# Inverter.net
KiCad netlist of a schematic drawn in Altium Designer
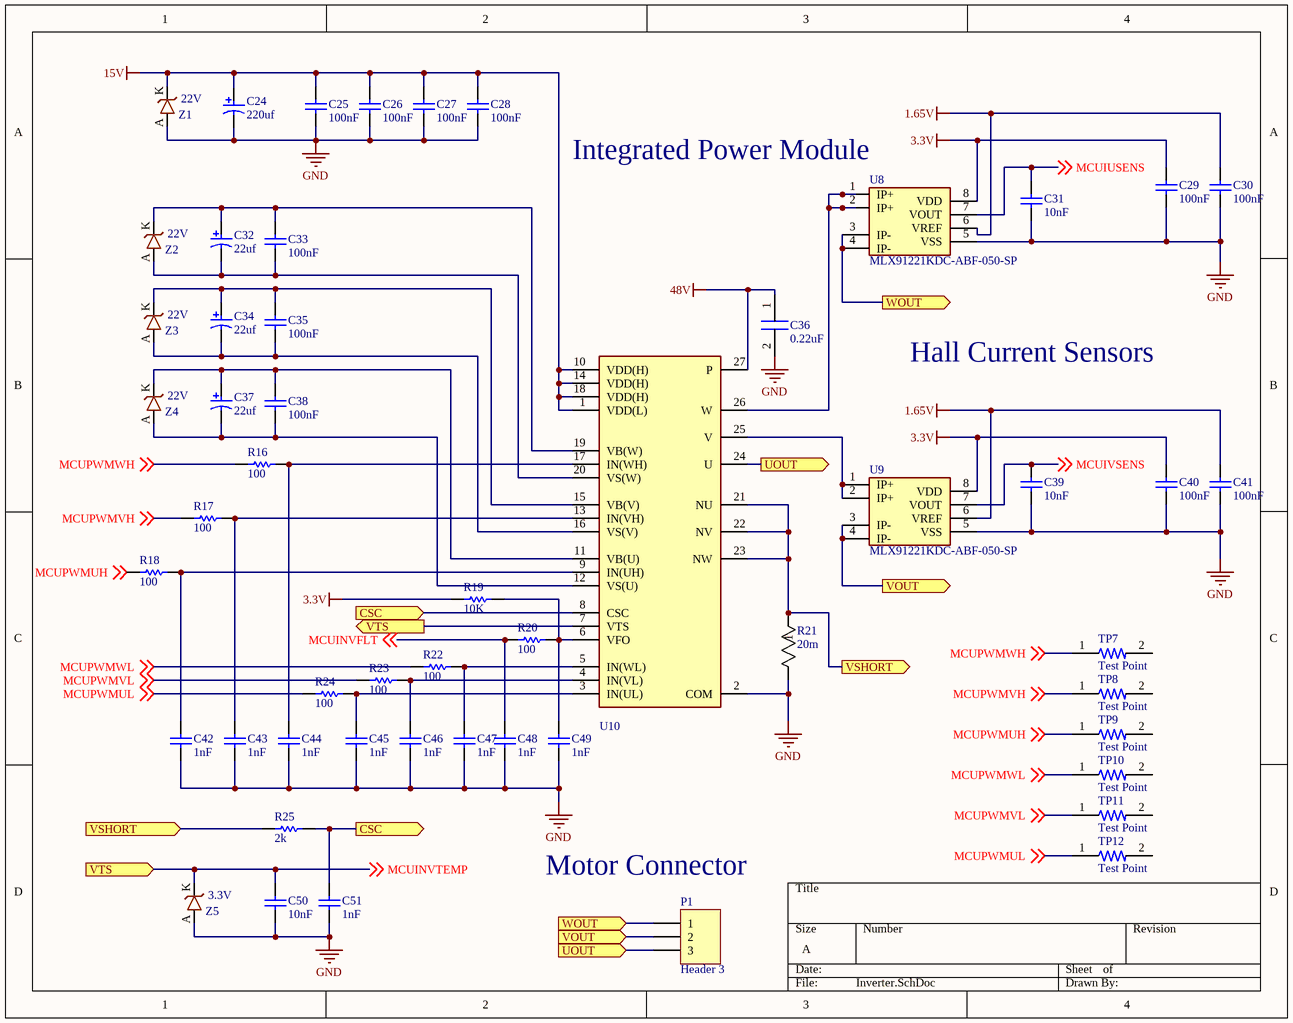
[diagram p0: Inverter.SchDoc]

(export (version "E")
  (design (tool "Eeschema 10.0.6"))
  (components
    (comp (ref "C24")
      (value "220uf")
      (footprint "PNSC-ECA-1VM221-2")
      (description "Aluminum Electrolytic Capacitor, 220 uF, +/- 20%, 35 V, -40 to 85 degC, 2-Pin THD, RoHS, Bulk")
      (fields (field (name "MANUFACTURER") "Panasonic"))
      (libsource (lib "Altium Content Vault") (part "CAP-P-2"))
    )
    (comp (ref "C25")
      (value "100nF")
      (footprint "CAPC1609X100X15LL20")
      (fields
        (field (name "MANUFACTURER") "AVX Interconnect / Elco")
        (field (name "PART NUMBER") "TACL105M006XTA")
      )
      (libsource (lib "Altium Content Vault") (part "CAP"))
    )
    (comp (ref "C26")
      (value "100nF")
      (footprint "CAPC1609X100X15LL20")
      (fields
        (field (name "MANUFACTURER") "AVX Interconnect / Elco")
        (field (name "PART NUMBER") "TACL105M006XTA")
      )
      (libsource (lib "Altium Content Vault") (part "CAP"))
    )
    (comp (ref "C27")
      (value "100nF")
      (footprint "CAPC1609X100X15LL20")
      (fields
        (field (name "MANUFACTURER") "AVX Interconnect / Elco")
        (field (name "PART NUMBER") "TACL105M006XTA")
      )
      (libsource (lib "Altium Content Vault") (part "CAP"))
    )
    (comp (ref "C28")
      (value "100nF")
      (footprint "CAPC1609X100X15LL20")
      (fields
        (field (name "MANUFACTURER") "AVX Interconnect / Elco")
        (field (name "PART NUMBER") "TACL105M006XTA")
      )
      (libsource (lib "Altium Content Vault") (part "CAP"))
    )
    (comp (ref "C29")
      (value "100nF")
      (footprint "CAPC1609X100X15LL20")
      (fields
        (field (name "MANUFACTURER") "AVX Interconnect / Elco")
        (field (name "PART NUMBER") "TACL105M006XTA")
      )
      (libsource (lib "Altium Content Vault") (part "CAP"))
    )
    (comp (ref "C30")
      (value "100nF")
      (footprint "CAPC1609X100X15LL20")
      (fields
        (field (name "MANUFACTURER") "AVX Interconnect / Elco")
        (field (name "PART NUMBER") "TACL105M006XTA")
      )
      (libsource (lib "Altium Content Vault") (part "CAP"))
    )
    (comp (ref "C31")
      (value "10nF")
      (footprint "CAPC1609X100X15LL20")
      (fields
        (field (name "MANUFACTURER") "AVX Interconnect / Elco")
        (field (name "PART NUMBER") "TACL105M006XTA")
      )
      (libsource (lib "Altium Content Vault") (part "CAP"))
    )
    (comp (ref "C32")
      (value "22uf")
      (footprint "CAPPR55-200-1100X500X1200")
      (description "Aluminum Electrolytic Capacitor, 22 uF, +/- 20%, 50 V, -40 to 85 degC, 2-Pin THD, RoHS, Bulk")
      (fields (field (name "VOLTAGE") "50V") (field (name "MANUFACTURER") "Panasonic"))
      (libsource (lib "Altium Content Vault") (part "CAP-P-2"))
    )
    (comp (ref "C33")
      (value "100nF")
      (footprint "CAPC1609X100X15LL20")
      (fields
        (field (name "MANUFACTURER") "AVX Interconnect / Elco")
        (field (name "PART NUMBER") "TACL105M006XTA")
      )
      (libsource (lib "Altium Content Vault") (part "CAP"))
    )
    (comp (ref "C34")
      (value "22uf")
      (footprint "CAPPR55-200-1100X500X1200")
      (description "Aluminum Electrolytic Capacitor, 22 uF, +/- 20%, 50 V, -40 to 85 degC, 2-Pin THD, RoHS, Bulk")
      (fields (field (name "VOLTAGE") "50V") (field (name "MANUFACTURER") "Panasonic"))
      (libsource (lib "Altium Content Vault") (part "CAP-P-2"))
    )
    (comp (ref "C35")
      (value "100nF")
      (footprint "CAPC1609X100X15LL20")
      (fields
        (field (name "MANUFACTURER") "AVX Interconnect / Elco")
        (field (name "PART NUMBER") "TACL105M006XTA")
      )
      (libsource (lib "Altium Content Vault") (part "CAP"))
    )
    (comp (ref "C36")
      (value "0.22uF")
      (footprint "B32652A3224K000")
      (description "Capacitor, Film, 15mm leads")
      (libsource (lib "ee_453_yourname") (part "B32652A3224K000"))
    )
    (comp (ref "C37")
      (value "22uf")
      (footprint "CAPPR55-200-1100X500X1200")
      (description "Aluminum Electrolytic Capacitor, 22 uF, +/- 20%, 50 V, -40 to 85 degC, 2-Pin THD, RoHS, Bulk")
      (fields (field (name "VOLTAGE") "50V") (field (name "MANUFACTURER") "Panasonic"))
      (libsource (lib "Altium Content Vault") (part "CAP-P-2"))
    )
    (comp (ref "C38")
      (value "100nF")
      (footprint "CAPC1609X100X15LL20")
      (fields
        (field (name "MANUFACTURER") "AVX Interconnect / Elco")
        (field (name "PART NUMBER") "TACL105M006XTA")
      )
      (libsource (lib "Altium Content Vault") (part "CAP"))
    )
    (comp (ref "C39")
      (value "10nF")
      (footprint "CAPC1609X100X15LL20")
      (fields
        (field (name "MANUFACTURER") "AVX Interconnect / Elco")
        (field (name "PART NUMBER") "TACL105M006XTA")
      )
      (libsource (lib "Altium Content Vault") (part "CAP"))
    )
    (comp (ref "C40")
      (value "100nF")
      (footprint "CAPC1609X100X15LL20")
      (fields
        (field (name "MANUFACTURER") "AVX Interconnect / Elco")
        (field (name "PART NUMBER") "TACL105M006XTA")
      )
      (libsource (lib "Altium Content Vault") (part "CAP"))
    )
    (comp (ref "C41")
      (value "100nF")
      (footprint "CAPC1609X100X15LL20")
      (fields
        (field (name "MANUFACTURER") "AVX Interconnect / Elco")
        (field (name "PART NUMBER") "TACL105M006XTA")
      )
      (libsource (lib "Altium Content Vault") (part "CAP"))
    )
    (comp (ref "C42")
      (value "1nF")
      (footprint "CAPC1609X100X15LL20")
      (fields
        (field (name "MANUFACTURER") "AVX Interconnect / Elco")
        (field (name "PART NUMBER") "TACL105M006XTA")
      )
      (libsource (lib "Altium Content Vault") (part "CAP"))
    )
    (comp (ref "C43")
      (value "1nF")
      (footprint "CAPC1609X100X15LL20")
      (fields
        (field (name "MANUFACTURER") "AVX Interconnect / Elco")
        (field (name "PART NUMBER") "TACL105M006XTA")
      )
      (libsource (lib "Altium Content Vault") (part "CAP"))
    )
    (comp (ref "C44")
      (value "1nF")
      (footprint "CAPC1609X100X15LL20")
      (fields
        (field (name "MANUFACTURER") "AVX Interconnect / Elco")
        (field (name "PART NUMBER") "TACL105M006XTA")
      )
      (libsource (lib "Altium Content Vault") (part "CAP"))
    )
    (comp (ref "C45")
      (value "1nF")
      (footprint "CAPC1609X100X15LL20")
      (fields
        (field (name "MANUFACTURER") "AVX Interconnect / Elco")
        (field (name "PART NUMBER") "TACL105M006XTA")
      )
      (libsource (lib "Altium Content Vault") (part "CAP"))
    )
    (comp (ref "C46")
      (value "1nF")
      (footprint "CAPC1609X100X15LL20")
      (fields
        (field (name "MANUFACTURER") "AVX Interconnect / Elco")
        (field (name "PART NUMBER") "TACL105M006XTA")
      )
      (libsource (lib "Altium Content Vault") (part "CAP"))
    )
    (comp (ref "C47")
      (value "1nF")
      (footprint "CAPC1609X100X15LL20")
      (fields
        (field (name "MANUFACTURER") "AVX Interconnect / Elco")
        (field (name "PART NUMBER") "TACL105M006XTA")
      )
      (libsource (lib "Altium Content Vault") (part "CAP"))
    )
    (comp (ref "C48")
      (value "1nF")
      (footprint "CAPC1609X100X15LL20")
      (fields
        (field (name "MANUFACTURER") "AVX Interconnect / Elco")
        (field (name "PART NUMBER") "TACL105M006XTA")
      )
      (libsource (lib "Altium Content Vault") (part "CAP"))
    )
    (comp (ref "C49")
      (value "1nF")
      (footprint "CAPC1609X100X15LL20")
      (fields
        (field (name "MANUFACTURER") "AVX Interconnect / Elco")
        (field (name "PART NUMBER") "TACL105M006XTA")
      )
      (libsource (lib "Altium Content Vault") (part "CAP"))
    )
    (comp (ref "C50")
      (value "10nF")
      (footprint "CAPC1609X100X15LL20")
      (fields
        (field (name "MANUFACTURER") "AVX Interconnect / Elco")
        (field (name "PART NUMBER") "TACL105M006XTA")
      )
      (libsource (lib "Altium Content Vault") (part "CAP"))
    )
    (comp (ref "C51")
      (value "1nF")
      (footprint "CAPC1609X100X15LL20")
      (fields
        (field (name "MANUFACTURER") "AVX Interconnect / Elco")
        (field (name "PART NUMBER") "TACL105M006XTA")
      )
      (libsource (lib "Altium Content Vault") (part "CAP"))
    )
    (comp (ref "P1")
      (value "Header 3")
      (footprint "3-Pin TB 5mm Pitch")
      (description "Header, 3-Pin")
      (fields (field (name "PUBLISHER") "Altium Limited"))
      (libsource (lib "Miscellaneous Connectors") (part "Header 3"))
    )
    (comp (ref "R16")
      (value "100")
      (footprint "RESC1609X50X30NL8T20")
      (description "Chip Resistor, 0 Ohm, Jumper, 100 mW, -55 to 155 degC, 0603 (1608 Metric), RoHS, Tape and Reel")
      (fields (field (name "MANUFACTURER") "Vishay Semiconductor"))
      (libsource (lib "Altium Content Vault") (part "RES-2"))
    )
    (comp (ref "R17")
      (value "100")
      (footprint "RESC1609X50X30NL8T20")
      (description "Chip Resistor, 0 Ohm, Jumper, 100 mW, -55 to 155 degC, 0603 (1608 Metric), RoHS, Tape and Reel")
      (fields (field (name "MANUFACTURER") "Vishay Semiconductor"))
      (libsource (lib "Altium Content Vault") (part "RES-2"))
    )
    (comp (ref "R18")
      (value "100")
      (footprint "RESC1609X50X30NL8T20")
      (description "Chip Resistor, 0 Ohm, Jumper, 100 mW, -55 to 155 degC, 0603 (1608 Metric), RoHS, Tape and Reel")
      (fields (field (name "MANUFACTURER") "Vishay Semiconductor"))
      (libsource (lib "Altium Content Vault") (part "RES-2"))
    )
    (comp (ref "R19")
      (value "10K")
      (footprint "RESC1609X50X30NL8T20")
      (description "Chip Resistor, 0 Ohm, Jumper, 100 mW, -55 to 155 degC, 0603 (1608 Metric), RoHS, Tape and Reel")
      (fields (field (name "MANUFACTURER") "Vishay Semiconductor"))
      (libsource (lib "Altium Content Vault") (part "RES-2"))
    )
    (comp (ref "R20")
      (value "100")
      (footprint "RESC1609X50X30NL8T20")
      (description "Chip Resistor, 0 Ohm, Jumper, 100 mW, -55 to 155 degC, 0603 (1608 Metric), RoHS, Tape and Reel")
      (fields (field (name "MANUFACTURER") "Vishay Semiconductor"))
      (libsource (lib "Altium Content Vault") (part "RES-2"))
    )
    (comp (ref "R21")
      (value "20m")
      (footprint "RES_BR3_STP")
      (description "No Description Available")
      (fields
        (field (name "MANUFACTURER_PART_NUMBER") "BR3FB5L00")
        (field (name "COPYRIGHT") "Copyright (C) 2022 Ultra Librarian. All rights reserved.")
      )
      (libsource (lib "BR3FB5L00") (part "BR3FB5L00"))
    )
    (comp (ref "R22")
      (value "100")
      (footprint "RESC1609X50X30NL8T20")
      (description "Chip Resistor, 0 Ohm, Jumper, 100 mW, -55 to 155 degC, 0603 (1608 Metric), RoHS, Tape and Reel")
      (fields (field (name "MANUFACTURER") "Vishay Semiconductor"))
      (libsource (lib "Altium Content Vault") (part "RES-2"))
    )
    (comp (ref "R23")
      (value "100")
      (footprint "RESC1609X50X30NL8T20")
      (description "Chip Resistor, 0 Ohm, Jumper, 100 mW, -55 to 155 degC, 0603 (1608 Metric), RoHS, Tape and Reel")
      (fields (field (name "MANUFACTURER") "Vishay Semiconductor"))
      (libsource (lib "Altium Content Vault") (part "RES-2"))
    )
    (comp (ref "R24")
      (value "100")
      (footprint "RESC1609X50X30NL8T20")
      (description "Chip Resistor, 0 Ohm, Jumper, 100 mW, -55 to 155 degC, 0603 (1608 Metric), RoHS, Tape and Reel")
      (fields (field (name "MANUFACTURER") "Vishay Semiconductor"))
      (libsource (lib "Altium Content Vault") (part "RES-2"))
    )
    (comp (ref "R25")
      (value "2k")
      (footprint "RESC1609X50X30NL8T20")
      (description "Chip Resistor, 0 Ohm, Jumper, 100 mW, -55 to 155 degC, 0603 (1608 Metric), RoHS, Tape and Reel")
      (fields (field (name "MANUFACTURER") "Vishay Semiconductor"))
      (libsource (lib "Altium Content Vault") (part "RES-2"))
    )
    (comp (ref "TP7")
      (value "Test Point")
      (footprint "RESC3216X70N")
      (description "PC Test Point , Plating Surface Mount Mounting Type")
      (fields (field (name "MF") "KOA Speer") (field (name "MP") "RCWCTE"))
      (libsource (lib "SnapEDAsch") (part "RCWCTE"))
    )
    (comp (ref "TP8")
      (value "Test Point")
      (footprint "RESC3216X70N")
      (description "PC Test Point , Plating Surface Mount Mounting Type")
      (fields (field (name "MF") "KOA Speer") (field (name "MP") "RCWCTE"))
      (libsource (lib "SnapEDAsch") (part "RCWCTE"))
    )
    (comp (ref "TP9")
      (value "Test Point")
      (footprint "RESC3216X70N")
      (description "PC Test Point , Plating Surface Mount Mounting Type")
      (fields (field (name "MF") "KOA Speer") (field (name "MP") "RCWCTE"))
      (libsource (lib "SnapEDAsch") (part "RCWCTE"))
    )
    (comp (ref "TP10")
      (value "Test Point")
      (footprint "RESC3216X70N")
      (description "PC Test Point , Plating Surface Mount Mounting Type")
      (fields (field (name "MF") "KOA Speer") (field (name "MP") "RCWCTE"))
      (libsource (lib "SnapEDAsch") (part "RCWCTE"))
    )
    (comp (ref "TP11")
      (value "Test Point")
      (footprint "RESC3216X70N")
      (description "PC Test Point , Plating Surface Mount Mounting Type")
      (fields (field (name "MF") "KOA Speer") (field (name "MP") "RCWCTE"))
      (libsource (lib "SnapEDAsch") (part "RCWCTE"))
    )
    (comp (ref "TP12")
      (value "Test Point")
      (footprint "RESC3216X70N")
      (description "PC Test Point , Plating Surface Mount Mounting Type")
      (fields (field (name "MF") "KOA Speer") (field (name "MP") "RCWCTE"))
      (libsource (lib "SnapEDAsch") (part "RCWCTE"))
    )
    (comp (ref "U8")
      (value "MLX91221KDC-ABF-050-SP")
      (footprint "SOIC8")
      (description "Hall Current Sensor")
      (libsource (lib "ee_453_yourname") (part "MLX91221KDC-ABF-050-SP"))
    )
    (comp (ref "U9")
      (value "MLX91221KDC-ABF-050-SP")
      (footprint "SOIC8")
      (description "Hall Current Sensor")
      (libsource (lib "ee_453_yourname") (part "MLX91221KDC-ABF-050-SP"))
    )
    (comp (ref "U10")
      (value "FNB34060T")
      (footprint "FNB34060T")
      (libsource (lib "ee_453_yourname") (part "FNB34060T"))
    )
    (comp (ref "Z1")
      (value "22V")
      (footprint "DO-214AA")
      (description "Zener Diode, DO-214AA")
      (libsource (lib "ee_453_yourname") (part "D"))
    )
    (comp (ref "Z2")
      (value "22V")
      (footprint "DO-214AA")
      (description "Zener Diode, DO-214AA")
      (libsource (lib "ee_453_yourname") (part "D"))
    )
    (comp (ref "Z3")
      (value "22V")
      (footprint "DO-214AA")
      (description "Zener Diode, DO-214AA")
      (libsource (lib "ee_453_yourname") (part "D"))
    )
    (comp (ref "Z4")
      (value "22V")
      (footprint "DO-214AA")
      (description "Zener Diode, DO-214AA")
      (libsource (lib "ee_453_yourname") (part "D"))
    )
    (comp (ref "Z5")
      (value "3.3V")
      (footprint "SOD123")
      (description "Zener Diode, SOD123")
      (libsource (lib "ee_453_yourname") (part "SOD123"))
    )
  )
  (nets
    (net (code "1") (name "/CSC") (class "Default")
      (node (ref "C51") (pin "2") (pinfunction "2_2") (pintype "passive"))
      (node (ref "R25") (pin "1") (pinfunction "1_1") (pintype "passive"))
      (node (ref "U10") (pin "8") (pinfunction "CSC_8") (pintype "passive"))
    )
    (net (code "2") (name "/UOUT") (class "Default")
      (node (ref "P1") (pin "3") (pinfunction "3_3") (pintype "passive"))
      (node (ref "U10") (pin "24") (pinfunction "U_24") (pintype "passive"))
    )
    (net (code "3") (name "/VOUT") (class "Default")
      (node (ref "P1") (pin "2") (pinfunction "2_2") (pintype "passive"))
      (node (ref "U9") (pin "3") (pinfunction "IP-_3") (pintype "passive"))
      (node (ref "U9") (pin "4") (pinfunction "IP-_4") (pintype "passive"))
    )
    (net (code "4") (name "/VSHORT") (class "Default")
      (node (ref "R21") (pin "1") (pinfunction "1_1") (pintype "passive"))
      (node (ref "R25") (pin "2") (pinfunction "2_2") (pintype "passive"))
      (node (ref "U10") (pin "21") (pinfunction "NU_21") (pintype "passive"))
      (node (ref "U10") (pin "22") (pinfunction "NV_22") (pintype "passive"))
      (node (ref "U10") (pin "23") (pinfunction "NW_23") (pintype "passive"))
    )
    (net (code "5") (name "/WOUT") (class "Default")
      (node (ref "P1") (pin "1") (pinfunction "1_1") (pintype "passive"))
      (node (ref "U8") (pin "3") (pinfunction "IP-_3") (pintype "passive"))
      (node (ref "U8") (pin "4") (pinfunction "IP-_4") (pintype "passive"))
    )
    (net (code "6") (name "1.65V") (class "Default")
      (node (ref "C30") (pin "2") (pinfunction "2_2") (pintype "passive"))
      (node (ref "C41") (pin "2") (pinfunction "2_2") (pintype "passive"))
      (node (ref "U8") (pin "6") (pinfunction "VREF_6") (pintype "passive"))
      (node (ref "U9") (pin "6") (pinfunction "VREF_6") (pintype "passive"))
    )
    (net (code "7") (name "3.3V") (class "Default")
      (node (ref "C29") (pin "2") (pinfunction "2_2") (pintype "passive"))
      (node (ref "C40") (pin "2") (pinfunction "2_2") (pintype "passive"))
      (node (ref "R19") (pin "2") (pinfunction "2_2") (pintype "passive"))
      (node (ref "U8") (pin "8") (pinfunction "VDD_8") (pintype "passive"))
      (node (ref "U9") (pin "8") (pinfunction "VDD_8") (pintype "passive"))
    )
    (net (code "8") (name "15V") (class "Default")
      (node (ref "C24") (pin "1") (pinfunction "1_1") (pintype "passive"))
      (node (ref "C25") (pin "2") (pinfunction "2_2") (pintype "passive"))
      (node (ref "C26") (pin "2") (pinfunction "2_2") (pintype "passive"))
      (node (ref "C27") (pin "2") (pinfunction "2_2") (pintype "passive"))
      (node (ref "C28") (pin "2") (pinfunction "2_2") (pintype "passive"))
      (node (ref "U10") (pin "1") (pinfunction "VDD(L)_1") (pintype "power_in"))
      (node (ref "U10") (pin "10") (pinfunction "VDD(H)_10") (pintype "power_in"))
      (node (ref "U10") (pin "14") (pinfunction "VDD(H)_14") (pintype "power_in"))
      (node (ref "U10") (pin "18") (pinfunction "VDD(H)_18") (pintype "power_in"))
      (node (ref "Z1") (pin "K") (pintype "passive"))
    )
    (net (code "9") (name "48V") (class "Default")
      (node (ref "C36") (pin "1") (pintype "passive"))
      (node (ref "U10") (pin "27") (pinfunction "P_27") (pintype "passive"))
    )
    (net (code "10") (name "GND") (class "Default")
      (node (ref "C24") (pin "2") (pinfunction "2_2") (pintype "passive"))
      (node (ref "C25") (pin "1") (pinfunction "1_1") (pintype "passive"))
      (node (ref "C26") (pin "1") (pinfunction "1_1") (pintype "passive"))
      (node (ref "C27") (pin "1") (pinfunction "1_1") (pintype "passive"))
      (node (ref "C28") (pin "1") (pinfunction "1_1") (pintype "passive"))
      (node (ref "C29") (pin "1") (pinfunction "1_1") (pintype "passive"))
      (node (ref "C30") (pin "1") (pinfunction "1_1") (pintype "passive"))
      (node (ref "C31") (pin "1") (pinfunction "1_1") (pintype "passive"))
      (node (ref "C36") (pin "2") (pintype "passive"))
      (node (ref "C39") (pin "1") (pinfunction "1_1") (pintype "passive"))
      (node (ref "C40") (pin "1") (pinfunction "1_1") (pintype "passive"))
      (node (ref "C41") (pin "1") (pinfunction "1_1") (pintype "passive"))
      (node (ref "C42") (pin "1") (pinfunction "1_1") (pintype "passive"))
      (node (ref "C43") (pin "1") (pinfunction "1_1") (pintype "passive"))
      (node (ref "C44") (pin "1") (pinfunction "1_1") (pintype "passive"))
      (node (ref "C45") (pin "1") (pinfunction "1_1") (pintype "passive"))
      (node (ref "C46") (pin "1") (pinfunction "1_1") (pintype "passive"))
      (node (ref "C47") (pin "1") (pinfunction "1_1") (pintype "passive"))
      (node (ref "C48") (pin "1") (pinfunction "1_1") (pintype "passive"))
      (node (ref "C49") (pin "1") (pinfunction "1_1") (pintype "passive"))
      (node (ref "C50") (pin "1") (pinfunction "1_1") (pintype "passive"))
      (node (ref "C51") (pin "1") (pinfunction "1_1") (pintype "passive"))
      (node (ref "R21") (pin "2") (pinfunction "2_2") (pintype "passive"))
      (node (ref "U10") (pin "2") (pinfunction "COM_2") (pintype "power_in"))
      (node (ref "U8") (pin "5") (pinfunction "VSS_5") (pintype "passive"))
      (node (ref "U9") (pin "5") (pinfunction "VSS_5") (pintype "passive"))
      (node (ref "Z1") (pin "A") (pintype "passive"))
      (node (ref "Z5") (pin "A") (pintype "passive"))
    )
    (net (code "11") (name "MCUINVFLT") (class "Default")
      (node (ref "C48") (pin "2") (pinfunction "2_2") (pintype "passive"))
      (node (ref "R20") (pin "2") (pinfunction "2_2") (pintype "passive"))
    )
    (net (code "12") (name "MCUINVTEMP") (class "Default")
      (node (ref "C50") (pin "2") (pinfunction "2_2") (pintype "passive"))
      (node (ref "U10") (pin "7") (pinfunction "VTS_7") (pintype "passive"))
      (node (ref "Z5") (pin "K") (pintype "passive"))
    )
    (net (code "13") (name "MCUIUSENS") (class "Default")
      (node (ref "C31") (pin "2") (pinfunction "2_2") (pintype "passive"))
      (node (ref "U8") (pin "7") (pinfunction "VOUT_7") (pintype "passive"))
    )
    (net (code "14") (name "MCUIVSENS") (class "Default")
      (node (ref "C39") (pin "2") (pinfunction "2_2") (pintype "passive"))
      (node (ref "U9") (pin "7") (pinfunction "VOUT_7") (pintype "passive"))
    )
    (net (code "15") (name "MCUPWMUH") (class "Default")
      (node (ref "R18") (pin "2") (pinfunction "2_2") (pintype "passive"))
      (node (ref "TP9") (pin "1") (pinfunction "1_1") (pintype "passive"))
    )
    (net (code "16") (name "MCUPWMUL") (class "Default")
      (node (ref "R24") (pin "2") (pinfunction "2_2") (pintype "passive"))
      (node (ref "TP12") (pin "1") (pinfunction "1_1") (pintype "passive"))
    )
    (net (code "17") (name "MCUPWMVH") (class "Default")
      (node (ref "R17") (pin "2") (pinfunction "2_2") (pintype "passive"))
      (node (ref "TP8") (pin "1") (pinfunction "1_1") (pintype "passive"))
    )
    (net (code "18") (name "MCUPWMVL") (class "Default")
      (node (ref "R23") (pin "2") (pinfunction "2_2") (pintype "passive"))
      (node (ref "TP11") (pin "1") (pinfunction "1_1") (pintype "passive"))
    )
    (net (code "19") (name "MCUPWMWH") (class "Default")
      (node (ref "R16") (pin "2") (pinfunction "2_2") (pintype "passive"))
      (node (ref "TP7") (pin "1") (pinfunction "1_1") (pintype "passive"))
    )
    (net (code "20") (name "MCUPWMWL") (class "Default")
      (node (ref "R22") (pin "2") (pinfunction "2_2") (pintype "passive"))
      (node (ref "TP10") (pin "1") (pinfunction "1_1") (pintype "passive"))
    )
    (net (code "21") (name "Net-(U10-IN(UH))") (class "Default")
      (node (ref "C42") (pin "2") (pinfunction "2_2") (pintype "passive"))
      (node (ref "R18") (pin "1") (pinfunction "1_1") (pintype "passive"))
      (node (ref "U10") (pin "9") (pinfunction "IN(UH)_9") (pintype "passive"))
    )
    (net (code "22") (name "Net-(U10-IN(UL))") (class "Default")
      (node (ref "C45") (pin "2") (pinfunction "2_2") (pintype "passive"))
      (node (ref "R24") (pin "1") (pinfunction "1_1") (pintype "passive"))
      (node (ref "U10") (pin "3") (pinfunction "IN(UL)_3") (pintype "passive"))
    )
    (net (code "23") (name "Net-(U10-IN(VH))") (class "Default")
      (node (ref "C43") (pin "2") (pinfunction "2_2") (pintype "passive"))
      (node (ref "R17") (pin "1") (pinfunction "1_1") (pintype "passive"))
      (node (ref "U10") (pin "13") (pinfunction "IN(VH)_13") (pintype "passive"))
    )
    (net (code "24") (name "Net-(U10-IN(VL))") (class "Default")
      (node (ref "C46") (pin "2") (pinfunction "2_2") (pintype "passive"))
      (node (ref "R23") (pin "1") (pinfunction "1_1") (pintype "passive"))
      (node (ref "U10") (pin "4") (pinfunction "IN(VL)_4") (pintype "passive"))
    )
    (net (code "25") (name "Net-(U10-IN(WH))") (class "Default")
      (node (ref "C44") (pin "2") (pinfunction "2_2") (pintype "passive"))
      (node (ref "R16") (pin "1") (pinfunction "1_1") (pintype "passive"))
      (node (ref "U10") (pin "17") (pinfunction "IN(WH)_17") (pintype "passive"))
    )
    (net (code "26") (name "Net-(U10-IN(WL))") (class "Default")
      (node (ref "C47") (pin "2") (pinfunction "2_2") (pintype "passive"))
      (node (ref "R22") (pin "1") (pinfunction "1_1") (pintype "passive"))
      (node (ref "U10") (pin "5") (pinfunction "IN(WL)_5") (pintype "passive"))
    )
    (net (code "27") (name "Net-(U10-V)") (class "Default")
      (node (ref "U10") (pin "25") (pinfunction "V_25") (pintype "passive"))
      (node (ref "U9") (pin "1") (pinfunction "IP+_1") (pintype "passive"))
      (node (ref "U9") (pin "2") (pinfunction "IP+_2") (pintype "passive"))
    )
    (net (code "28") (name "Net-(U10-VB(U))") (class "Default")
      (node (ref "C37") (pin "1") (pinfunction "1_1") (pintype "passive"))
      (node (ref "C38") (pin "2") (pinfunction "2_2") (pintype "passive"))
      (node (ref "U10") (pin "11") (pinfunction "VB(U)_11") (pintype "power_in"))
      (node (ref "Z4") (pin "K") (pintype "passive"))
    )
    (net (code "29") (name "Net-(U10-VB(V))") (class "Default")
      (node (ref "C34") (pin "1") (pinfunction "1_1") (pintype "passive"))
      (node (ref "C35") (pin "2") (pinfunction "2_2") (pintype "passive"))
      (node (ref "U10") (pin "15") (pinfunction "VB(V)_15") (pintype "power_in"))
      (node (ref "Z3") (pin "K") (pintype "passive"))
    )
    (net (code "30") (name "Net-(U10-VB(W))") (class "Default")
      (node (ref "C32") (pin "1") (pinfunction "1_1") (pintype "passive"))
      (node (ref "C33") (pin "2") (pinfunction "2_2") (pintype "passive"))
      (node (ref "U10") (pin "19") (pinfunction "VB(W)_19") (pintype "power_in"))
      (node (ref "Z2") (pin "K") (pintype "passive"))
    )
    (net (code "31") (name "Net-(U10-VFO)") (class "Default")
      (node (ref "C49") (pin "2") (pinfunction "2_2") (pintype "passive"))
      (node (ref "R19") (pin "1") (pinfunction "1_1") (pintype "passive"))
      (node (ref "R20") (pin "1") (pinfunction "1_1") (pintype "passive"))
      (node (ref "U10") (pin "6") (pinfunction "VFO_6") (pintype "passive"))
    )
    (net (code "32") (name "Net-(U10-VS(U))") (class "Default")
      (node (ref "C37") (pin "2") (pinfunction "2_2") (pintype "passive"))
      (node (ref "C38") (pin "1") (pinfunction "1_1") (pintype "passive"))
      (node (ref "U10") (pin "12") (pinfunction "VS(U)_12") (pintype "power_in"))
      (node (ref "Z4") (pin "A") (pintype "passive"))
    )
    (net (code "33") (name "Net-(U10-VS(V))") (class "Default")
      (node (ref "C34") (pin "2") (pinfunction "2_2") (pintype "passive"))
      (node (ref "C35") (pin "1") (pinfunction "1_1") (pintype "passive"))
      (node (ref "U10") (pin "16") (pinfunction "VS(V)_16") (pintype "power_in"))
      (node (ref "Z3") (pin "A") (pintype "passive"))
    )
    (net (code "34") (name "Net-(U10-VS(W))") (class "Default")
      (node (ref "C32") (pin "2") (pinfunction "2_2") (pintype "passive"))
      (node (ref "C33") (pin "1") (pinfunction "1_1") (pintype "passive"))
      (node (ref "U10") (pin "20") (pinfunction "VS(W)_20") (pintype "power_in"))
      (node (ref "Z2") (pin "A") (pintype "passive"))
    )
    (net (code "35") (name "Net-(U10-W)") (class "Default")
      (node (ref "U10") (pin "26") (pinfunction "W_26") (pintype "passive"))
      (node (ref "U8") (pin "1") (pinfunction "IP+_1") (pintype "passive"))
      (node (ref "U8") (pin "2") (pinfunction "IP+_2") (pintype "passive"))
    )
    (net (code "36") (name "unconnected-(TP7-Pad2)") (class "Default")
      (node (ref "TP7") (pin "2") (pinfunction "2_2") (pintype "passive"))
    )
    (net (code "37") (name "unconnected-(TP8-Pad2)") (class "Default")
      (node (ref "TP8") (pin "2") (pinfunction "2_2") (pintype "passive"))
    )
    (net (code "38") (name "unconnected-(TP9-Pad2)") (class "Default")
      (node (ref "TP9") (pin "2") (pinfunction "2_2") (pintype "passive"))
    )
    (net (code "39") (name "unconnected-(TP10-Pad2)") (class "Default")
      (node (ref "TP10") (pin "2") (pinfunction "2_2") (pintype "passive"))
    )
    (net (code "40") (name "unconnected-(TP11-Pad2)") (class "Default")
      (node (ref "TP11") (pin "2") (pinfunction "2_2") (pintype "passive"))
    )
    (net (code "41") (name "unconnected-(TP12-Pad2)") (class "Default")
      (node (ref "TP12") (pin "2") (pinfunction "2_2") (pintype "passive"))
    )
  )
)
